# m_knife_1.net
KiCad netlist of a schematic drawn in EAGLE
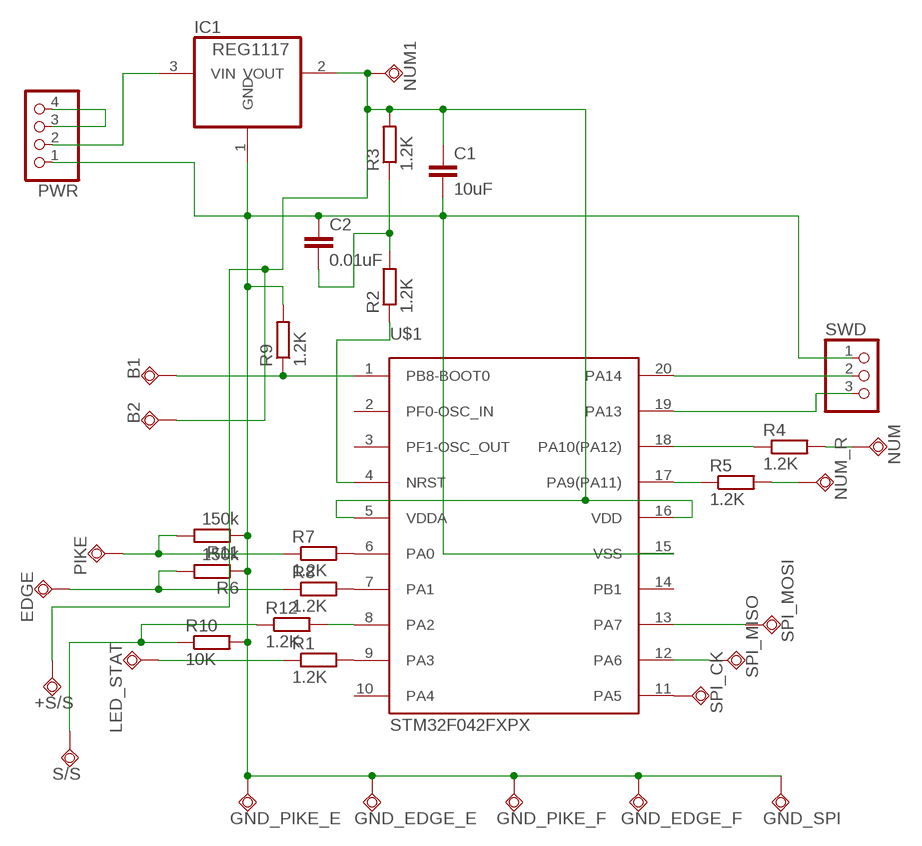
[diagram p0: schematic, sheet 1]

(export (version "E")
  (design (tool "Eeschema 10.0.6"))
  (components
    (comp (ref "+S/S")
      (value "TPSQTP20R")
      (footprint "eagle-import:TP20R")
      (libsource (lib "eagle-import") (part "TPSQTP20R"))
    )
    (comp (ref "B1")
      (value "TPSQTP20R")
      (footprint "eagle-import:TP20R")
      (libsource (lib "eagle-import") (part "TPSQTP20R"))
    )
    (comp (ref "B2")
      (value "TPSQTP20R")
      (footprint "eagle-import:TP20R")
      (libsource (lib "eagle-import") (part "TPSQTP20R"))
    )
    (comp (ref "C1")
      (value "10uF")
      (footprint "eagle-import:C0805")
      (libsource (lib "eagle-import") (part "C-EUC0805"))
    )
    (comp (ref "C2")
      (value "0.01uF")
      (footprint "eagle-import:C0805")
      (libsource (lib "eagle-import") (part "C-EUC0805"))
    )
    (comp (ref "EDGE")
      (value "TPSQTP20R")
      (footprint "eagle-import:TP20R")
      (libsource (lib "eagle-import") (part "TPSQTP20R"))
    )
    (comp (ref "GND_EDGE_E")
      (value "TPSQTP20R")
      (footprint "eagle-import:TP20R")
      (libsource (lib "eagle-import") (part "TPSQTP20R"))
    )
    (comp (ref "GND_EDGE_F")
      (value "TPSQTP20R")
      (footprint "eagle-import:TP20R")
      (libsource (lib "eagle-import") (part "TPSQTP20R"))
    )
    (comp (ref "GND_PIKE_E")
      (value "TPSQTP20R")
      (footprint "eagle-import:TP20R")
      (libsource (lib "eagle-import") (part "TPSQTP20R"))
    )
    (comp (ref "GND_PIKE_F")
      (value "TPSQTP20R")
      (footprint "eagle-import:TP20R")
      (libsource (lib "eagle-import") (part "TPSQTP20R"))
    )
    (comp (ref "GND_SPI")
      (value "TPSQTP20R")
      (footprint "eagle-import:TP20R")
      (libsource (lib "eagle-import") (part "TPSQTP20R"))
    )
    (comp (ref "IC1")
      (value "REG1117")
      (footprint "eagle-import:SOT223")
      (libsource (lib "eagle-import") (part "REG1117"))
    )
    (comp (ref "LED_STAT")
      (value "TPSQTP20R")
      (footprint "eagle-import:TP20R")
      (libsource (lib "eagle-import") (part "TPSQTP20R"))
    )
    (comp (ref "NUM")
      (value "TPSQTP20R")
      (footprint "eagle-import:TP20R")
      (libsource (lib "eagle-import") (part "TPSQTP20R"))
    )
    (comp (ref "NUM1")
      (value "TPSQTP20R")
      (footprint "eagle-import:TP20R")
      (libsource (lib "eagle-import") (part "TPSQTP20R"))
    )
    (comp (ref "NUM_R")
      (value "TPSQTP20R")
      (footprint "eagle-import:TP20R")
      (libsource (lib "eagle-import") (part "TPSQTP20R"))
    )
    (comp (ref "PIKE")
      (value "TPSQTP20R")
      (footprint "eagle-import:TP20R")
      (libsource (lib "eagle-import") (part "TPSQTP20R"))
    )
    (comp (ref "PWR")
      (value "PINHD-1X4")
      (footprint "eagle-import:1X04")
      (libsource (lib "eagle-import") (part "PINHD-1X4"))
    )
    (comp (ref "R1")
      (value "1.2K")
      (footprint "eagle-import:R0805")
      (libsource (lib "eagle-import") (part "R-EU_R0805"))
    )
    (comp (ref "R2")
      (value "1.2K")
      (footprint "eagle-import:R0805")
      (libsource (lib "eagle-import") (part "R-EU_R0805"))
    )
    (comp (ref "R3")
      (value "1.2K")
      (footprint "eagle-import:R0805")
      (libsource (lib "eagle-import") (part "R-EU_R0805"))
    )
    (comp (ref "R4")
      (value "1.2K")
      (footprint "eagle-import:R0805")
      (libsource (lib "eagle-import") (part "R-EU_R0805"))
    )
    (comp (ref "R5")
      (value "1.2K")
      (footprint "eagle-import:R0805")
      (libsource (lib "eagle-import") (part "R-EU_R0805"))
    )
    (comp (ref "R6")
      (value "150k")
      (footprint "eagle-import:R0805")
      (libsource (lib "eagle-import") (part "R-EU_R0805"))
    )
    (comp (ref "R7")
      (value "1.2K")
      (footprint "eagle-import:R0805")
      (libsource (lib "eagle-import") (part "R-EU_R0805"))
    )
    (comp (ref "R8")
      (value "1.2K")
      (footprint "eagle-import:R0805")
      (libsource (lib "eagle-import") (part "R-EU_R0805"))
    )
    (comp (ref "R9")
      (value "1.2K")
      (footprint "eagle-import:R0805")
      (libsource (lib "eagle-import") (part "R-EU_R0805"))
    )
    (comp (ref "R10")
      (value "10K")
      (footprint "eagle-import:R0805")
      (libsource (lib "eagle-import") (part "R-EU_R0805"))
    )
    (comp (ref "R11")
      (value "150k")
      (footprint "eagle-import:R0805")
      (libsource (lib "eagle-import") (part "R-EU_R0805"))
    )
    (comp (ref "R12")
      (value "1.2K")
      (footprint "eagle-import:R0805")
      (libsource (lib "eagle-import") (part "R-EU_R0805"))
    )
    (comp (ref "S/S")
      (value "TPSQTP20R")
      (footprint "eagle-import:TP20R")
      (libsource (lib "eagle-import") (part "TPSQTP20R"))
    )
    (comp (ref "SPI_CK")
      (value "TPSQTP20R")
      (footprint "eagle-import:TP20R")
      (libsource (lib "eagle-import") (part "TPSQTP20R"))
    )
    (comp (ref "SPI_MISO")
      (value "TPSQTP20R")
      (footprint "eagle-import:TP20R")
      (libsource (lib "eagle-import") (part "TPSQTP20R"))
    )
    (comp (ref "SPI_MOSI")
      (value "TPSQTP20R")
      (footprint "eagle-import:TP20R")
      (libsource (lib "eagle-import") (part "TPSQTP20R"))
    )
    (comp (ref "SWD")
      (value "PINHD-1X3")
      (footprint "eagle-import:1X03")
      (libsource (lib "eagle-import") (part "PINHD-1X3"))
    )
    (comp (ref "U$1")
      (value "STM32F042FXPX")
      (footprint "eagle-import:TSSOP20")
      (libsource (lib "eagle-import") (part "STM32F042FXPX"))
    )
  )
  (nets
    (net (code "1") (name "Net-(C2-Pad2)") (class "Default")
      (node (ref "C2") (pin "2") (pinfunction "2_2") (pintype "passive"))
      (node (ref "R2") (pin "2") (pinfunction "2_2") (pintype "passive"))
      (node (ref "R3") (pin "1") (pinfunction "1_1") (pintype "passive"))
    )
    (net (code "2") (name "Net-(EDGE-PadTP)") (class "Default")
      (node (ref "EDGE") (pin "TP") (pinfunction "TP_TP") (pintype "input"))
      (node (ref "R6") (pin "2") (pinfunction "2_2") (pintype "passive"))
      (node (ref "R8") (pin "1") (pinfunction "1_1") (pintype "passive"))
    )
    (net (code "3") (name "Net-(IC1-GND)") (class "Default")
      (node (ref "C1") (pin "2") (pinfunction "2_2") (pintype "passive"))
      (node (ref "C2") (pin "1") (pinfunction "1_1") (pintype "passive"))
      (node (ref "GND_EDGE_E") (pin "TP") (pinfunction "TP_TP") (pintype "input"))
      (node (ref "GND_EDGE_F") (pin "TP") (pinfunction "TP_TP") (pintype "input"))
      (node (ref "GND_PIKE_E") (pin "TP") (pinfunction "TP_TP") (pintype "input"))
      (node (ref "GND_PIKE_F") (pin "TP") (pinfunction "TP_TP") (pintype "input"))
      (node (ref "GND_SPI") (pin "TP") (pinfunction "TP_TP") (pintype "input"))
      (node (ref "IC1") (pin "1") (pinfunction "GND_1") (pintype "power_in"))
      (node (ref "PWR") (pin "1") (pinfunction "1_1") (pintype "passive"))
      (node (ref "R10") (pin "2") (pinfunction "2_2") (pintype "passive"))
      (node (ref "R11") (pin "1") (pinfunction "1_1") (pintype "passive"))
      (node (ref "R6") (pin "1") (pinfunction "1_1") (pintype "passive"))
      (node (ref "R9") (pin "2") (pinfunction "2_2") (pintype "passive"))
      (node (ref "SWD") (pin "1") (pinfunction "1_1") (pintype "passive"))
      (node (ref "U$1") (pin "15") (pinfunction "VSS_15") (pintype "bidirectional"))
    )
    (net (code "4") (name "Net-(IC1-VIN)") (class "Default")
      (node (ref "IC1") (pin "3") (pinfunction "VIN_3") (pintype "input"))
      (node (ref "PWR") (pin "2") (pinfunction "2_2") (pintype "passive"))
    )
    (net (code "5") (name "Net-(IC1-VOUT)") (class "Default")
      (node (ref "+S/S") (pin "TP") (pinfunction "TP_TP") (pintype "input"))
      (node (ref "B2") (pin "TP") (pinfunction "TP_TP") (pintype "input"))
      (node (ref "C1") (pin "1") (pinfunction "1_1") (pintype "passive"))
      (node (ref "IC1") (pin "2") (pinfunction "VOUT_2") (pintype "output"))
      (node (ref "NUM1") (pin "TP") (pinfunction "TP_TP") (pintype "input"))
      (node (ref "R3") (pin "2") (pinfunction "2_2") (pintype "passive"))
      (node (ref "U$1") (pin "16") (pinfunction "VDD_16") (pintype "bidirectional"))
      (node (ref "U$1") (pin "5") (pinfunction "VDDA_5") (pintype "bidirectional"))
    )
    (net (code "6") (name "Net-(LED_STAT-PadTP)") (class "Default")
      (node (ref "LED_STAT") (pin "TP") (pinfunction "TP_TP") (pintype "input"))
      (node (ref "R1") (pin "1") (pinfunction "1_1") (pintype "passive"))
    )
    (net (code "7") (name "Net-(NUM-PadTP)") (class "Default")
      (node (ref "NUM") (pin "TP") (pinfunction "TP_TP") (pintype "input"))
      (node (ref "R4") (pin "2") (pinfunction "2_2") (pintype "passive"))
    )
    (net (code "8") (name "Net-(NUM_R-PadTP)") (class "Default")
      (node (ref "NUM_R") (pin "TP") (pinfunction "TP_TP") (pintype "input"))
      (node (ref "R5") (pin "2") (pinfunction "2_2") (pintype "passive"))
    )
    (net (code "9") (name "Net-(PIKE-PadTP)") (class "Default")
      (node (ref "PIKE") (pin "TP") (pinfunction "TP_TP") (pintype "input"))
      (node (ref "R11") (pin "2") (pinfunction "2_2") (pintype "passive"))
      (node (ref "R7") (pin "1") (pinfunction "1_1") (pintype "passive"))
    )
    (net (code "10") (name "Net-(PWR-Pad3)") (class "Default")
      (node (ref "PWR") (pin "3") (pinfunction "3_3") (pintype "passive"))
      (node (ref "PWR") (pin "4") (pinfunction "4_4") (pintype "passive"))
    )
    (net (code "11") (name "Net-(R10-Pad1)") (class "Default")
      (node (ref "R10") (pin "1") (pinfunction "1_1") (pintype "passive"))
      (node (ref "R12") (pin "1") (pinfunction "1_1") (pintype "passive"))
      (node (ref "S/S") (pin "TP") (pinfunction "TP_TP") (pintype "input"))
    )
    (net (code "12") (name "Net-(U$1-NRST)") (class "Default")
      (node (ref "R2") (pin "1") (pinfunction "1_1") (pintype "passive"))
      (node (ref "U$1") (pin "4") (pinfunction "NRST_4") (pintype "bidirectional"))
    )
    (net (code "13") (name "Net-(U$1-PA0)") (class "Default")
      (node (ref "R7") (pin "2") (pinfunction "2_2") (pintype "passive"))
      (node (ref "U$1") (pin "6") (pinfunction "PA0_6") (pintype "bidirectional"))
    )
    (net (code "14") (name "Net-(U$1-PA1)") (class "Default")
      (node (ref "R8") (pin "2") (pinfunction "2_2") (pintype "passive"))
      (node (ref "U$1") (pin "7") (pinfunction "PA1_7") (pintype "bidirectional"))
    )
    (net (code "15") (name "Net-(U$1-PA2)") (class "Default")
      (node (ref "R12") (pin "2") (pinfunction "2_2") (pintype "passive"))
      (node (ref "U$1") (pin "8") (pinfunction "PA2_8") (pintype "bidirectional"))
    )
    (net (code "16") (name "Net-(U$1-PA3)") (class "Default")
      (node (ref "R1") (pin "2") (pinfunction "2_2") (pintype "passive"))
      (node (ref "U$1") (pin "9") (pinfunction "PA3_9") (pintype "bidirectional"))
    )
    (net (code "17") (name "Net-(U$1-PA5)") (class "Default")
      (node (ref "SPI_CK") (pin "TP") (pinfunction "TP_TP") (pintype "input"))
      (node (ref "U$1") (pin "11") (pinfunction "PA5_11") (pintype "bidirectional"))
    )
    (net (code "18") (name "Net-(U$1-PA6)") (class "Default")
      (node (ref "SPI_MISO") (pin "TP") (pinfunction "TP_TP") (pintype "input"))
      (node (ref "U$1") (pin "12") (pinfunction "PA6_12") (pintype "bidirectional"))
    )
    (net (code "19") (name "Net-(U$1-PA7)") (class "Default")
      (node (ref "SPI_MOSI") (pin "TP") (pinfunction "TP_TP") (pintype "input"))
      (node (ref "U$1") (pin "13") (pinfunction "PA7_13") (pintype "bidirectional"))
    )
    (net (code "20") (name "Net-(U$1-PA9(PA11))") (class "Default")
      (node (ref "R5") (pin "1") (pinfunction "1_1") (pintype "passive"))
      (node (ref "U$1") (pin "17") (pinfunction "PA9(PA11)_17") (pintype "bidirectional"))
    )
    (net (code "21") (name "Net-(U$1-PA10(PA12))") (class "Default")
      (node (ref "R4") (pin "1") (pinfunction "1_1") (pintype "passive"))
      (node (ref "U$1") (pin "18") (pinfunction "PA10(PA12)_18") (pintype "bidirectional"))
    )
    (net (code "22") (name "Net-(U$1-PA13)") (class "Default")
      (node (ref "SWD") (pin "3") (pinfunction "3_3") (pintype "passive"))
      (node (ref "U$1") (pin "19") (pinfunction "PA13_19") (pintype "bidirectional"))
    )
    (net (code "23") (name "Net-(U$1-PA14)") (class "Default")
      (node (ref "SWD") (pin "2") (pinfunction "2_2") (pintype "passive"))
      (node (ref "U$1") (pin "20") (pinfunction "PA14_20") (pintype "bidirectional"))
    )
    (net (code "24") (name "Net-(U$1-PB8-BOOT0)") (class "Default")
      (node (ref "B1") (pin "TP") (pinfunction "TP_TP") (pintype "input"))
      (node (ref "R9") (pin "1") (pinfunction "1_1") (pintype "passive"))
      (node (ref "U$1") (pin "1") (pinfunction "PB8-BOOT0_1") (pintype "bidirectional"))
    )
    (net (code "25") (name "unconnected-(U$1-PA4-Pad10)") (class "Default")
      (node (ref "U$1") (pin "10") (pinfunction "PA4_10") (pintype "bidirectional"))
    )
    (net (code "26") (name "unconnected-(U$1-PB1-Pad14)") (class "Default")
      (node (ref "U$1") (pin "14") (pinfunction "PB1_14") (pintype "bidirectional"))
    )
    (net (code "27") (name "unconnected-(U$1-PF0-OSC_IN-Pad2)") (class "Default")
      (node (ref "U$1") (pin "2") (pinfunction "PF0-OSC_IN_2") (pintype "bidirectional"))
    )
    (net (code "28") (name "unconnected-(U$1-PF1-OSC_OUT-Pad3)") (class "Default")
      (node (ref "U$1") (pin "3") (pinfunction "PF1-OSC_OUT_3") (pintype "bidirectional"))
    )
  )
)
